# rapidshark-main-breakout-top-mk-1_8.net
KiCad netlist of a schematic drawn in EAGLE
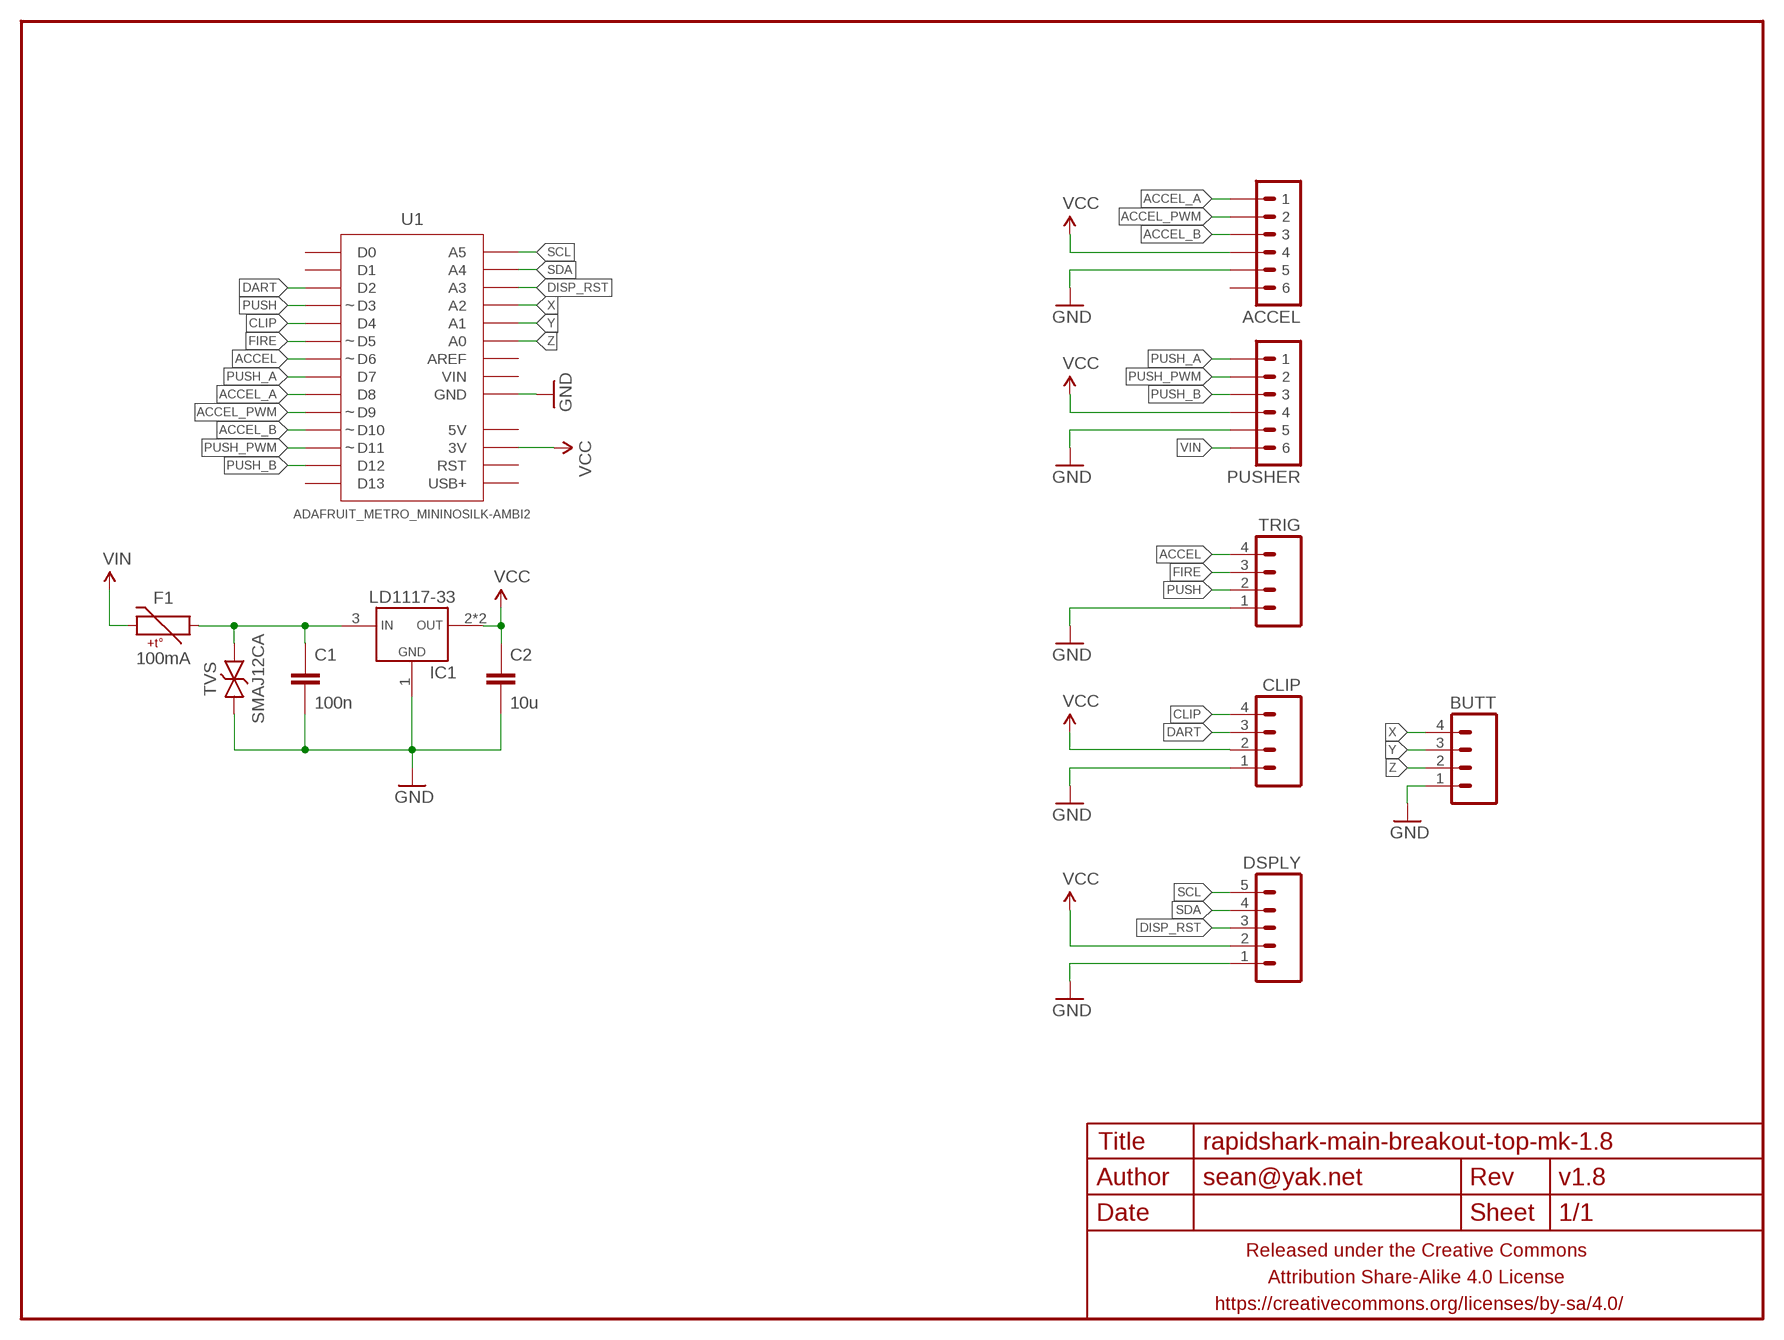
[diagram p0: schematic, sheet 1]

(export (version "E")
  (design (tool "Eeschema 10.0.6"))
  (components
    (comp (ref "ACCEL")
      (value "M06JST-PH-PTH-VERT")
      (footprint "eagle-import:JST-6-PH-VERT-PTH")
      (libsource (lib "eagle-import") (part "M06JST-PH-PTH-VERT"))
    )
    (comp (ref "BUTT")
      (value "M04JST-PTH-VERT")
      (footprint "eagle-import:JST-4-PH-VERT-PTH")
      (libsource (lib "eagle-import") (part "M04JST-PTH-VERT"))
    )
    (comp (ref "C1")
      (value "100n")
      (footprint "eagle-import:C0805")
      (libsource (lib "eagle-import") (part "CAPACITOR-CERAMICC0805"))
    )
    (comp (ref "C2")
      (value "10u")
      (footprint "eagle-import:C0805")
      (libsource (lib "eagle-import") (part "CAPACITOR-CERAMICC0805"))
    )
    (comp (ref "CLIP")
      (value "M04JST-PTH-VERT")
      (footprint "eagle-import:JST-4-PH-VERT-PTH")
      (libsource (lib "eagle-import") (part "M04JST-PTH-VERT"))
    )
    (comp (ref "DSPLY")
      (value "M05JST-PH-VERT-PTH")
      (footprint "eagle-import:JST-5-PH-VERT-PTH")
      (libsource (lib "eagle-import") (part "M05JST-PH-VERT-PTH"))
    )
    (comp (ref "F1")
      (value "100mA")
      (footprint "eagle-import:PTC-1206")
      (libsource (lib "eagle-import") (part "PTCSMD"))
    )
    (comp (ref "FRAME1")
      (value "FRAME-LETTERNO_PACKAGE")
      (footprint "eagle-import:DUMMY")
      (fields (field (name "DESIGNER") "sean@yak.net") (field (name "VERSION") "v1.8"))
      (libsource (lib "eagle-import") (part "FRAME-LETTERNO_PACKAGE"))
    )
    (comp (ref "IC1")
      (value "LD1117-33")
      (footprint "eagle-import:SOT223")
      (libsource (lib "eagle-import") (part "VREG_1117SOT223"))
    )
    (comp (ref "PUSHER")
      (value "M06JST-PH-PTH-VERT")
      (footprint "eagle-import:JST-6-PH-VERT-PTH")
      (libsource (lib "eagle-import") (part "M06JST-PH-PTH-VERT"))
    )
    (comp (ref "TRIG")
      (value "M04JST-PTH-VERT")
      (footprint "eagle-import:JST-4-PH-VERT-PTH")
      (libsource (lib "eagle-import") (part "M04JST-PTH-VERT"))
    )
    (comp (ref "TVS")
      (value "SMAJ12CA")
      (footprint "eagle-import:SMA-DIODE-TVS-BIDIR")
      (libsource (lib "eagle-import") (part "TVSSMA"))
    )
    (comp (ref "U1")
      (value "ADAFRUIT_METRO_MININOSILK-AMBI2")
      (footprint "eagle-import:ADAFRUIT_METRO_MINI_BACK")
      (libsource (lib "eagle-import") (part "ADAFRUIT_METRO_MININOSILK-AMBI2"))
    )
  )
  (nets
    (net (code "1") (name "ACCEL") (class "Default")
      (node (ref "TRIG") (pin "4") (pinfunction "4_4") (pintype "passive"))
      (node (ref "U1") (pin "7") (pinfunction "D6_7") (pintype "bidirectional"))
    )
    (net (code "2") (name "ACCEL_A") (class "Default")
      (node (ref "ACCEL") (pin "1") (pinfunction "1_1") (pintype "passive"))
      (node (ref "U1") (pin "9") (pinfunction "D8_9") (pintype "bidirectional"))
    )
    (net (code "3") (name "ACCEL_B") (class "Default")
      (node (ref "ACCEL") (pin "3") (pinfunction "3_3") (pintype "passive"))
      (node (ref "U1") (pin "11") (pinfunction "D10_11") (pintype "bidirectional"))
    )
    (net (code "4") (name "ACCEL_PWM") (class "Default")
      (node (ref "ACCEL") (pin "2") (pinfunction "2_2") (pintype "passive"))
      (node (ref "U1") (pin "10") (pinfunction "D9_10") (pintype "bidirectional"))
    )
    (net (code "5") (name "CLIP") (class "Default")
      (node (ref "CLIP") (pin "4") (pinfunction "4_4") (pintype "passive"))
      (node (ref "U1") (pin "5") (pinfunction "D4_5") (pintype "bidirectional"))
    )
    (net (code "6") (name "DART") (class "Default")
      (node (ref "CLIP") (pin "3") (pinfunction "3_3") (pintype "passive"))
      (node (ref "U1") (pin "3") (pinfunction "D2_3") (pintype "bidirectional"))
    )
    (net (code "7") (name "DISP_RST") (class "Default")
      (node (ref "DSPLY") (pin "3") (pinfunction "3_3") (pintype "passive"))
      (node (ref "U1") (pin "26") (pinfunction "A3_26") (pintype "bidirectional"))
    )
    (net (code "8") (name "FIRE") (class "Default")
      (node (ref "TRIG") (pin "3") (pinfunction "3_3") (pintype "passive"))
      (node (ref "U1") (pin "6") (pinfunction "D5_6") (pintype "bidirectional"))
    )
    (net (code "9") (name "GND") (class "Default")
      (node (ref "ACCEL") (pin "5") (pinfunction "5_5") (pintype "passive"))
      (node (ref "BUTT") (pin "1") (pinfunction "1_1") (pintype "passive"))
      (node (ref "C1") (pin "2") (pinfunction "2_2") (pintype "passive"))
      (node (ref "C2") (pin "2") (pinfunction "2_2") (pintype "passive"))
      (node (ref "CLIP") (pin "1") (pinfunction "1_1") (pintype "passive"))
      (node (ref "DSPLY") (pin "1") (pinfunction "1_1") (pintype "passive"))
      (node (ref "IC1") (pin "1") (pinfunction "GND_1") (pintype "bidirectional"))
      (node (ref "PUSHER") (pin "5") (pinfunction "5_5") (pintype "passive"))
      (node (ref "TRIG") (pin "1") (pinfunction "1_1") (pintype "passive"))
      (node (ref "TVS") (pin "1") (pinfunction "1_1") (pintype "passive"))
      (node (ref "U1") (pin "19") (pinfunction "GND_19") (pintype "bidirectional"))
      (node (ref "U1") (pin "20") (pinfunction "GND_20") (pintype "bidirectional"))
    )
    (net (code "10") (name "Net-(IC1-VIN)") (class "Default")
      (node (ref "C1") (pin "1") (pinfunction "1_1") (pintype "passive"))
      (node (ref "F1") (pin "1") (pinfunction "1_1") (pintype "passive"))
      (node (ref "IC1") (pin "3") (pinfunction "VIN_3") (pintype "bidirectional"))
      (node (ref "TVS") (pin "2") (pinfunction "2_2") (pintype "passive"))
    )
    (net (code "11") (name "PUSH") (class "Default")
      (node (ref "TRIG") (pin "2") (pinfunction "2_2") (pintype "passive"))
      (node (ref "U1") (pin "4") (pinfunction "D3_4") (pintype "bidirectional"))
    )
    (net (code "12") (name "PUSH_A") (class "Default")
      (node (ref "PUSHER") (pin "1") (pinfunction "1_1") (pintype "passive"))
      (node (ref "U1") (pin "8") (pinfunction "D7_8") (pintype "bidirectional"))
    )
    (net (code "13") (name "PUSH_B") (class "Default")
      (node (ref "PUSHER") (pin "3") (pinfunction "3_3") (pintype "passive"))
      (node (ref "U1") (pin "13") (pinfunction "D12_13") (pintype "bidirectional"))
    )
    (net (code "14") (name "PUSH_PWM") (class "Default")
      (node (ref "PUSHER") (pin "2") (pinfunction "2_2") (pintype "passive"))
      (node (ref "U1") (pin "12") (pinfunction "D11_12") (pintype "bidirectional"))
    )
    (net (code "15") (name "SCL") (class "Default")
      (node (ref "DSPLY") (pin "5") (pinfunction "5_5") (pintype "passive"))
      (node (ref "U1") (pin "28") (pinfunction "A5_28") (pintype "bidirectional"))
    )
    (net (code "16") (name "SDA") (class "Default")
      (node (ref "DSPLY") (pin "4") (pinfunction "4_4") (pintype "passive"))
      (node (ref "U1") (pin "27") (pinfunction "A4_27") (pintype "bidirectional"))
    )
    (net (code "17") (name "VCC") (class "Default")
      (node (ref "ACCEL") (pin "4") (pinfunction "4_4") (pintype "passive"))
      (node (ref "C2") (pin "1") (pinfunction "1_1") (pintype "passive"))
      (node (ref "CLIP") (pin "2") (pinfunction "2_2") (pintype "passive"))
      (node (ref "DSPLY") (pin "2") (pinfunction "2_2") (pintype "passive"))
      (node (ref "IC1") (pin "2") (pinfunction "VOUT_2") (pintype "bidirectional"))
      (node (ref "IC1") (pin "4") (pinfunction "VOUT_4") (pintype "bidirectional"))
      (node (ref "PUSHER") (pin "4") (pinfunction "4_4") (pintype "passive"))
      (node (ref "U1") (pin "17") (pinfunction "3V_17") (pintype "bidirectional"))
    )
    (net (code "18") (name "VIN") (class "Default")
      (node (ref "F1") (pin "2") (pinfunction "2_2") (pintype "passive"))
      (node (ref "PUSHER") (pin "6") (pinfunction "6_6") (pintype "passive"))
    )
    (net (code "19") (name "X") (class "Default")
      (node (ref "BUTT") (pin "4") (pinfunction "4_4") (pintype "passive"))
      (node (ref "U1") (pin "25") (pinfunction "A2_25") (pintype "bidirectional"))
    )
    (net (code "20") (name "Y") (class "Default")
      (node (ref "BUTT") (pin "3") (pinfunction "3_3") (pintype "passive"))
      (node (ref "U1") (pin "24") (pinfunction "A1_24") (pintype "bidirectional"))
    )
    (net (code "21") (name "Z") (class "Default")
      (node (ref "BUTT") (pin "2") (pinfunction "2_2") (pintype "passive"))
      (node (ref "U1") (pin "23") (pinfunction "A0_23") (pintype "bidirectional"))
    )
    (net (code "22") (name "unconnected-(ACCEL-Pad6)") (class "Default")
      (node (ref "ACCEL") (pin "6") (pinfunction "6_6") (pintype "passive"))
    )
    (net (code "23") (name "unconnected-(U1-5V-Pad18)") (class "Default")
      (node (ref "U1") (pin "18") (pinfunction "5V_18") (pintype "bidirectional"))
    )
    (net (code "24") (name "unconnected-(U1-AREF-Pad22)") (class "Default")
      (node (ref "U1") (pin "22") (pinfunction "AREF_22") (pintype "bidirectional"))
    )
    (net (code "25") (name "unconnected-(U1-D0-Pad1)") (class "Default")
      (node (ref "U1") (pin "1") (pinfunction "D0_1") (pintype "bidirectional"))
    )
    (net (code "26") (name "unconnected-(U1-D1-Pad2)") (class "Default")
      (node (ref "U1") (pin "2") (pinfunction "D1_2") (pintype "bidirectional"))
    )
    (net (code "27") (name "unconnected-(U1-D13-Pad14)") (class "Default")
      (node (ref "U1") (pin "14") (pinfunction "D13_14") (pintype "bidirectional"))
    )
    (net (code "28") (name "unconnected-(U1-RST-Pad16)") (class "Default")
      (node (ref "U1") (pin "16") (pinfunction "RST_16") (pintype "bidirectional"))
    )
    (net (code "29") (name "unconnected-(U1-USB+-Pad15)") (class "Default")
      (node (ref "U1") (pin "15") (pinfunction "USB+_15") (pintype "bidirectional"))
    )
    (net (code "30") (name "unconnected-(U1-VIN-Pad21)") (class "Default")
      (node (ref "U1") (pin "21") (pinfunction "VIN_21") (pintype "bidirectional"))
    )
  )
)
